# Sens_SI7005.net
KiCad netlist of a schematic drawn in EAGLE
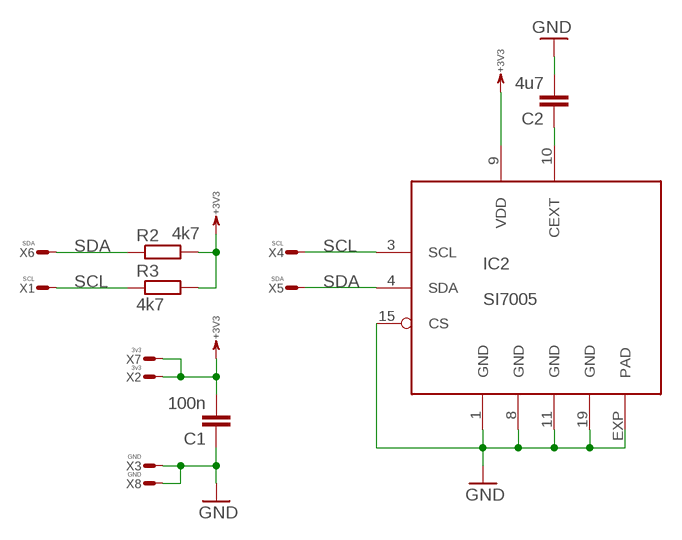
[diagram p0: schematic, sheet 1]

(export (version "E")
  (design (tool "Eeschema 10.0.6"))
  (components
    (comp (ref "C1")
      (value "100n")
      (footprint "eagle-import:0603")
      (libsource (lib "eagle-import") (part "C0603"))
    )
    (comp (ref "C2")
      (value "4u7")
      (footprint "eagle-import:0603")
      (libsource (lib "eagle-import") (part "C0603"))
    )
    (comp (ref "IC2")
      (value "SI7005")
      (footprint "eagle-import:QFN24")
      (libsource (lib "eagle-import") (part "SI7005"))
    )
    (comp (ref "R2")
      (value "4k7")
      (footprint "eagle-import:0603")
      (libsource (lib "eagle-import") (part "R0603"))
    )
    (comp (ref "R3")
      (value "4k7")
      (footprint "eagle-import:0603")
      (libsource (lib "eagle-import") (part "R0603"))
    )
    (comp (ref "X1")
      (value "SCL")
      (footprint "eagle-import:T1.6_0.9")
      (libsource (lib "eagle-import") (part "WIREPADT1.6/0.9"))
    )
    (comp (ref "X2")
      (value "3v3")
      (footprint "eagle-import:T1.6_0.9")
      (libsource (lib "eagle-import") (part "WIREPADT1.6/0.9"))
    )
    (comp (ref "X3")
      (value "GND")
      (footprint "eagle-import:T1.6_0.9")
      (libsource (lib "eagle-import") (part "WIREPADT1.6/0.9"))
    )
    (comp (ref "X4")
      (value "SCL")
      (footprint "eagle-import:T1.6_0.9")
      (libsource (lib "eagle-import") (part "WIREPADT1.6/0.9"))
    )
    (comp (ref "X5")
      (value "SDA")
      (footprint "eagle-import:T1.6_0.9")
      (libsource (lib "eagle-import") (part "WIREPADT1.6/0.9"))
    )
    (comp (ref "X6")
      (value "SDA")
      (footprint "eagle-import:T1.6_0.9")
      (libsource (lib "eagle-import") (part "WIREPADT1.6/0.9"))
    )
    (comp (ref "X7")
      (value "3v3")
      (footprint "eagle-import:T1.6_0.9")
      (libsource (lib "eagle-import") (part "WIREPADT1.6/0.9"))
    )
    (comp (ref "X8")
      (value "GND")
      (footprint "eagle-import:T1.6_0.9")
      (libsource (lib "eagle-import") (part "WIREPADT1.6/0.9"))
    )
  )
  (nets
    (net (code "1") (name "+3V3") (class "Default")
      (node (ref "C1") (pin "2") (pinfunction "2_2") (pintype "passive"))
      (node (ref "IC2") (pin "9") (pinfunction "VDD_9") (pintype "bidirectional"))
      (node (ref "R2") (pin "2") (pinfunction "2_2") (pintype "passive"))
      (node (ref "R3") (pin "2") (pinfunction "2_2") (pintype "passive"))
      (node (ref "X2") (pin "1") (pinfunction "S_1") (pintype "passive"))
      (node (ref "X7") (pin "1") (pinfunction "S_1") (pintype "passive"))
    )
    (net (code "2") (name "/SCL") (class "Default")
      (node (ref "IC2") (pin "3") (pinfunction "SCL_3") (pintype "bidirectional"))
      (node (ref "R3") (pin "1") (pinfunction "1_1") (pintype "passive"))
      (node (ref "X1") (pin "1") (pinfunction "S_1") (pintype "passive"))
      (node (ref "X4") (pin "1") (pinfunction "S_1") (pintype "passive"))
    )
    (net (code "3") (name "/SDA") (class "Default")
      (node (ref "IC2") (pin "4") (pinfunction "SDA_4") (pintype "bidirectional"))
      (node (ref "R2") (pin "1") (pinfunction "1_1") (pintype "passive"))
      (node (ref "X5") (pin "1") (pinfunction "S_1") (pintype "passive"))
      (node (ref "X6") (pin "1") (pinfunction "S_1") (pintype "passive"))
    )
    (net (code "4") (name "GND") (class "Default")
      (node (ref "C1") (pin "1") (pinfunction "1_1") (pintype "passive"))
      (node (ref "C2") (pin "2") (pinfunction "2_2") (pintype "passive"))
      (node (ref "IC2") (pin "1") (pinfunction "GND_1") (pintype "bidirectional"))
      (node (ref "IC2") (pin "11") (pinfunction "GND_11") (pintype "bidirectional"))
      (node (ref "IC2") (pin "15") (pinfunction "CS_15") (pintype "input"))
      (node (ref "IC2") (pin "19") (pinfunction "GND_19") (pintype "bidirectional"))
      (node (ref "IC2") (pin "8") (pinfunction "GND_8") (pintype "bidirectional"))
      (node (ref "IC2") (pin "EXP") (pinfunction "PAD_EXP") (pintype "bidirectional"))
      (node (ref "X3") (pin "1") (pinfunction "S_1") (pintype "passive"))
      (node (ref "X8") (pin "1") (pinfunction "S_1") (pintype "passive"))
    )
    (net (code "5") (name "Net-(IC2-CEXT)") (class "Default")
      (node (ref "C2") (pin "1") (pinfunction "1_1") (pintype "passive"))
      (node (ref "IC2") (pin "10") (pinfunction "CEXT_10") (pintype "bidirectional"))
    )
  )
)
